# NG2092_QWIIC.net
KiCad netlist of a schematic drawn in Altium Designer
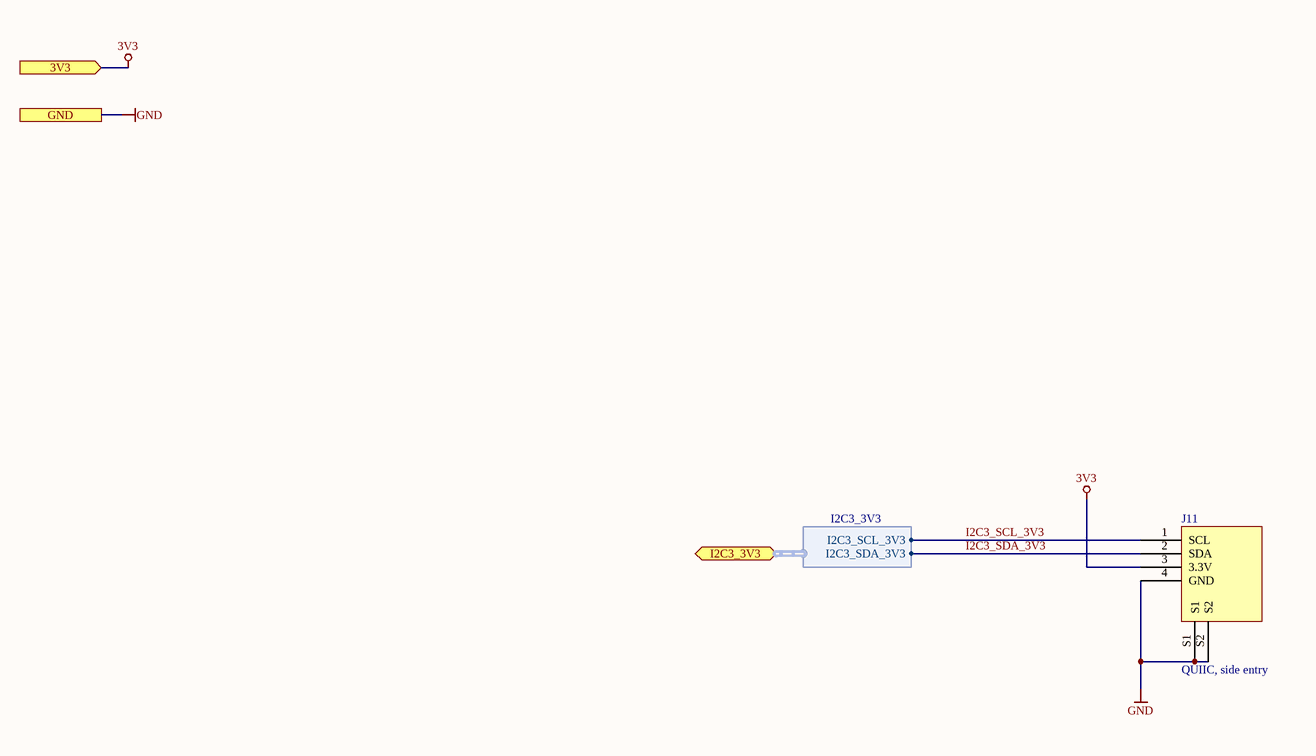
[diagram p0: NG2092_QWIIC.SchDoc]

(export (version "E")
  (design (tool "Eeschema 10.0.6"))
  (components
    (comp (ref "J11")
      (value "QUIIC, side entry")
      (footprint "SM04B-SRSS-TB(LF)(SN)")
      (description "Connector Header, Side Entry, SR Series, 4 Position, 1.00mm, 50V, Surface Mount, Tin, Natural")
      (libsource (lib "NG2092") (part "SM04B-SRSS-TB(LF)(SN)"))
    )
  )
  (nets
    (net (code "2") (name "/I2C3_SCL_3V3") (class "Default")
      (node (ref "J11") (pin "1") (pinfunction "SCL_1") (pintype "passive"))
    )
    (net (code "3") (name "/I2C3_SDA_3V3") (class "Default")
      (node (ref "J11") (pin "2") (pinfunction "SDA_2") (pintype "passive"))
    )
    (net (code "5") (name "3V3") (class "Default")
      (node (ref "J11") (pin "3") (pinfunction "3.3V_3") (pintype "passive"))
    )
    (net (code "6") (name "GND") (class "Default")
      (node (ref "J11") (pin "4") (pinfunction "GND_4") (pintype "passive"))
      (node (ref "J11") (pin "S1") (pinfunction "S1_S1") (pintype "passive"))
      (node (ref "J11") (pin "S2") (pinfunction "S2_S2") (pintype "passive"))
    )
  )
)
